# LP4-1.net
KiCad netlist of a schematic drawn in EAGLE
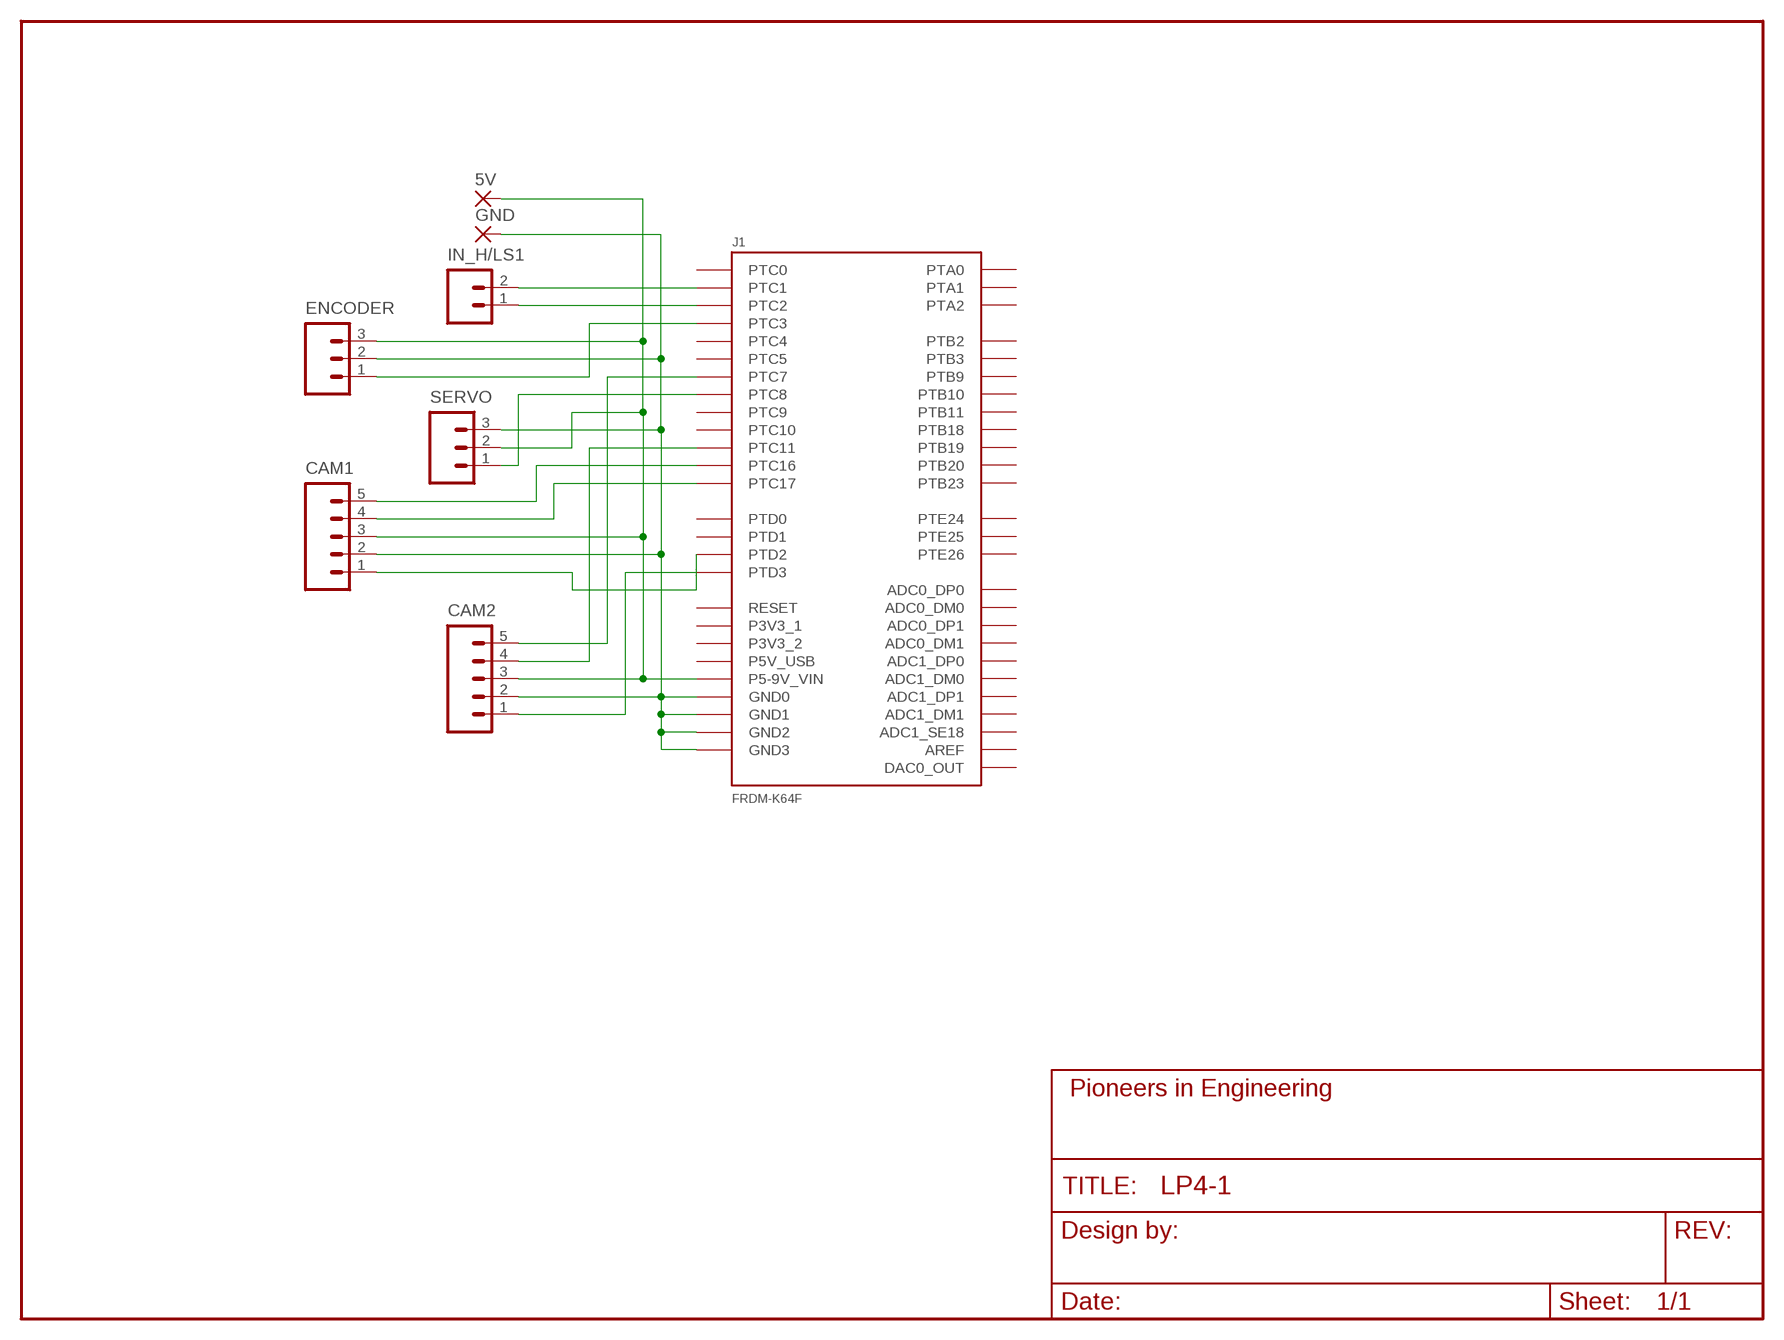
[diagram p0: schematic, sheet 1]

(export (version "E")
  (design (tool "Eeschema 10.0.6"))
  (components
    (comp (ref "5V")
      (value "3,17/1,3")
      (footprint "eagle-import:3,17_1,3")
      (libsource (lib "eagle-import") (part "3,17/1,3"))
    )
    (comp (ref "CAM1")
      (value "M05PTH")
      (footprint "eagle-import:1X05")
      (libsource (lib "eagle-import") (part "M05PTH"))
    )
    (comp (ref "CAM2")
      (value "M05PTH")
      (footprint "eagle-import:1X05")
      (libsource (lib "eagle-import") (part "M05PTH"))
    )
    (comp (ref "ENCODER")
      (value "M03PTH")
      (footprint "eagle-import:1X03")
      (libsource (lib "eagle-import") (part "M03PTH"))
    )
    (comp (ref "GND")
      (value "3,17/1,3")
      (footprint "eagle-import:3,17_1,3")
      (libsource (lib "eagle-import") (part "3,17/1,3"))
    )
    (comp (ref "IN_H/LS1")
      (value "M02PTH")
      (footprint "eagle-import:1X02")
      (libsource (lib "eagle-import") (part "M02PTH"))
    )
    (comp (ref "J1")
      (value "FRDM-K64F")
      (footprint "eagle-import:FRDM-K64F")
      (libsource (lib "eagle-import") (part "FRDM-K64F"))
    )
    (comp (ref "SERVO")
      (value "M03PTH")
      (footprint "eagle-import:1X03")
      (libsource (lib "eagle-import") (part "M03PTH"))
    )
  )
  (nets
    (net (code "1") (name "Net-(5V-P)") (class "Default")
      (node (ref "5V") (pin "1") (pinfunction "P_1") (pintype "passive"))
      (node (ref "CAM1") (pin "3") (pinfunction "3_3") (pintype "passive"))
      (node (ref "CAM2") (pin "3") (pinfunction "3_3") (pintype "passive"))
      (node (ref "ENCODER") (pin "3") (pinfunction "3_3") (pintype "passive"))
      (node (ref "J1") (pin "J3-16") (pinfunction "P5-9V_VIN_J3-16") (pintype "bidirectional"))
      (node (ref "SERVO") (pin "2") (pinfunction "2_2") (pintype "passive"))
    )
    (net (code "2") (name "Net-(GND-P)") (class "Default")
      (node (ref "CAM1") (pin "2") (pinfunction "2_2") (pintype "passive"))
      (node (ref "CAM2") (pin "2") (pinfunction "2_2") (pintype "passive"))
      (node (ref "ENCODER") (pin "2") (pinfunction "2_2") (pintype "passive"))
      (node (ref "GND") (pin "1") (pinfunction "P_1") (pintype "passive"))
      (node (ref "J1") (pin "J2-14") (pinfunction "GND1_J2-14") (pintype "bidirectional"))
      (node (ref "J1") (pin "J2-3") (pinfunction "GND0_J2-3") (pintype "bidirectional"))
      (node (ref "J1") (pin "J3-12") (pinfunction "GND2_J3-12") (pintype "bidirectional"))
      (node (ref "J1") (pin "J3-14") (pinfunction "GND3_J3-14") (pintype "bidirectional"))
      (node (ref "SERVO") (pin "3") (pinfunction "3_3") (pintype "passive"))
    )
    (net (code "3") (name "Net-(J1-PTC1)") (class "Default")
      (node (ref "IN_H/LS1") (pin "2") (pinfunction "2_2") (pintype "passive"))
      (node (ref "J1") (pin "J1-5") (pinfunction "PTC1_J1-5") (pintype "bidirectional"))
    )
    (net (code "4") (name "Net-(J1-PTC2)") (class "Default")
      (node (ref "IN_H/LS1") (pin "1") (pinfunction "1_1") (pintype "passive"))
      (node (ref "J1") (pin "J1-14") (pinfunction "PTC2_J1-14") (pintype "bidirectional"))
    )
    (net (code "5") (name "Net-(J1-PTC3)") (class "Default")
      (node (ref "ENCODER") (pin "1") (pinfunction "1_1") (pintype "passive"))
      (node (ref "J1") (pin "J1-16") (pinfunction "PTC3_J1-16") (pintype "bidirectional"))
    )
    (net (code "6") (name "Net-(J1-PTC7)") (class "Default")
      (node (ref "CAM2") (pin "5") (pinfunction "5_5") (pintype "passive"))
      (node (ref "J1") (pin "J1-13") (pinfunction "PTC7_J1-13") (pintype "bidirectional"))
    )
    (net (code "7") (name "Net-(J1-PTC8)") (class "Default")
      (node (ref "J1") (pin "J1-7") (pinfunction "PTC8_J1-7") (pintype "bidirectional"))
      (node (ref "SERVO") (pin "1") (pinfunction "1_1") (pintype "passive"))
    )
    (net (code "8") (name "Net-(J1-PTC11)") (class "Default")
      (node (ref "CAM2") (pin "4") (pinfunction "4_4") (pintype "passive"))
      (node (ref "J1") (pin "J4-10") (pinfunction "PTC11_J4-10") (pintype "bidirectional"))
    )
    (net (code "9") (name "Net-(J1-PTC16)") (class "Default")
      (node (ref "CAM1") (pin "5") (pinfunction "5_5") (pintype "passive"))
      (node (ref "J1") (pin "J1-2") (pinfunction "PTC16_J1-2") (pintype "bidirectional"))
    )
    (net (code "10") (name "Net-(J1-PTC17)") (class "Default")
      (node (ref "CAM1") (pin "4") (pinfunction "4_4") (pintype "passive"))
      (node (ref "J1") (pin "J1-4") (pinfunction "PTC17_J1-4") (pintype "bidirectional"))
    )
    (net (code "11") (name "Net-(J1-PTD2)") (class "Default")
      (node (ref "CAM1") (pin "1") (pinfunction "1_1") (pintype "passive"))
      (node (ref "J1") (pin "J2-8") (pinfunction "PTD2_J2-8") (pintype "bidirectional"))
    )
    (net (code "12") (name "Net-(J1-PTD3)") (class "Default")
      (node (ref "CAM2") (pin "1") (pinfunction "1_1") (pintype "passive"))
      (node (ref "J1") (pin "J2-10") (pinfunction "PTD3_J2-10") (pintype "bidirectional"))
    )
    (net (code "13") (name "unconnected-(J1-ADC0_DM0-PadJ2-7)") (class "Default")
      (node (ref "J1") (pin "J2-7") (pinfunction "ADC0_DM0_J2-7") (pintype "bidirectional"))
    )
    (net (code "14") (name "unconnected-(J1-ADC0_DM1-PadJ4-3)") (class "Default")
      (node (ref "J1") (pin "J4-3") (pinfunction "ADC0_DM1_J4-3") (pintype "bidirectional"))
    )
    (net (code "15") (name "unconnected-(J1-ADC0_DP0-PadJ2-5)") (class "Default")
      (node (ref "J1") (pin "J2-5") (pinfunction "ADC0_DP0_J2-5") (pintype "bidirectional"))
    )
    (net (code "16") (name "unconnected-(J1-ADC0_DP1-PadJ4-1)") (class "Default")
      (node (ref "J1") (pin "J4-1") (pinfunction "ADC0_DP1_J4-1") (pintype "bidirectional"))
    )
    (net (code "17") (name "unconnected-(J1-ADC1_DM0-PadJ2-13)") (class "Default")
      (node (ref "J1") (pin "J2-13") (pinfunction "ADC1_DM0_J2-13") (pintype "bidirectional"))
    )
    (net (code "18") (name "unconnected-(J1-ADC1_DM1-PadJ4-7)") (class "Default")
      (node (ref "J1") (pin "J4-7") (pinfunction "ADC1_DM1_J4-7") (pintype "bidirectional"))
    )
    (net (code "19") (name "unconnected-(J1-ADC1_DP0-PadJ2-11)") (class "Default")
      (node (ref "J1") (pin "J2-11") (pinfunction "ADC1_DP0_J2-11") (pintype "bidirectional"))
    )
    (net (code "20") (name "unconnected-(J1-ADC1_DP1-PadJ4-5)") (class "Default")
      (node (ref "J1") (pin "J4-5") (pinfunction "ADC1_DP1_J4-5") (pintype "bidirectional"))
    )
    (net (code "21") (name "unconnected-(J1-ADC1_SE18-PadJ2-17)") (class "Default")
      (node (ref "J1") (pin "J2-17") (pinfunction "ADC1_SE18_J2-17") (pintype "bidirectional"))
    )
    (net (code "22") (name "unconnected-(J1-AREF-PadJ2-16)") (class "Default")
      (node (ref "J1") (pin "J2-16") (pinfunction "AREF_J2-16") (pintype "bidirectional"))
    )
    (net (code "23") (name "unconnected-(J1-DAC0_OUT-PadJ4-11)") (class "Default")
      (node (ref "J1") (pin "J4-11") (pinfunction "DAC0_OUT_J4-11") (pintype "bidirectional"))
    )
    (net (code "24") (name "unconnected-(J1-P3V3_1-PadJ3-4)") (class "Default")
      (node (ref "J1") (pin "J3-4") (pinfunction "P3V3_1_J3-4") (pintype "bidirectional"))
    )
    (net (code "25") (name "unconnected-(J1-P3V3_2-PadJ3-8)") (class "Default")
      (node (ref "J1") (pin "J3-8") (pinfunction "P3V3_2_J3-8") (pintype "bidirectional"))
    )
    (net (code "26") (name "unconnected-(J1-P5V_USB-PadJ3-10)") (class "Default")
      (node (ref "J1") (pin "J3-10") (pinfunction "P5V_USB_J3-10") (pintype "bidirectional"))
    )
    (net (code "27") (name "unconnected-(J1-PTA0-PadJ2-2)") (class "Default")
      (node (ref "J1") (pin "J2-2") (pinfunction "PTA0_J2-2") (pintype "bidirectional"))
    )
    (net (code "28") (name "unconnected-(J1-PTA1-PadJ1-8)") (class "Default")
      (node (ref "J1") (pin "J1-8") (pinfunction "PTA1_J1-8") (pintype "bidirectional"))
    )
    (net (code "29") (name "unconnected-(J1-PTA2-PadJ1-12)") (class "Default")
      (node (ref "J1") (pin "J1-12") (pinfunction "PTA2_J1-12") (pintype "bidirectional"))
    )
    (net (code "30") (name "unconnected-(J1-PTB2-PadJ4-2)") (class "Default")
      (node (ref "J1") (pin "J4-2") (pinfunction "PTB2_J4-2") (pintype "bidirectional"))
    )
    (net (code "31") (name "unconnected-(J1-PTB3-PadJ4-4)") (class "Default")
      (node (ref "J1") (pin "J4-4") (pinfunction "PTB3_J4-4") (pintype "bidirectional"))
    )
    (net (code "32") (name "unconnected-(J1-PTB9-PadJ1-6)") (class "Default")
      (node (ref "J1") (pin "J1-6") (pinfunction "PTB9_J1-6") (pintype "bidirectional"))
    )
    (net (code "33") (name "unconnected-(J1-PTB10-PadJ4-6)") (class "Default")
      (node (ref "J1") (pin "J4-6") (pinfunction "PTB10_J4-6") (pintype "bidirectional"))
    )
    (net (code "34") (name "unconnected-(J1-PTB11-PadJ4-8)") (class "Default")
      (node (ref "J1") (pin "J4-8") (pinfunction "PTB11_J4-8") (pintype "bidirectional"))
    )
    (net (code "35") (name "unconnected-(J1-PTB18-PadJ1-1)") (class "Default")
      (node (ref "J1") (pin "J1-1") (pinfunction "PTB18_J1-1") (pintype "bidirectional"))
    )
    (net (code "36") (name "unconnected-(J1-PTB19-PadJ1-3)") (class "Default")
      (node (ref "J1") (pin "J1-3") (pinfunction "PTB19_J1-3") (pintype "bidirectional"))
    )
    (net (code "37") (name "unconnected-(J1-PTB20-PadJ4-9)") (class "Default")
      (node (ref "J1") (pin "J4-9") (pinfunction "PTB20_J4-9") (pintype "bidirectional"))
    )
    (net (code "38") (name "unconnected-(J1-PTB23-PadJ1-10)") (class "Default")
      (node (ref "J1") (pin "J1-10") (pinfunction "PTB23_J1-10") (pintype "bidirectional"))
    )
    (net (code "39") (name "unconnected-(J1-PTC0-PadJ1-11)") (class "Default")
      (node (ref "J1") (pin "J1-11") (pinfunction "PTC0_J1-11") (pintype "bidirectional"))
    )
    (net (code "40") (name "unconnected-(J1-PTC4-PadJ2-4)") (class "Default")
      (node (ref "J1") (pin "J2-4") (pinfunction "PTC4_J2-4") (pintype "bidirectional"))
    )
    (net (code "41") (name "unconnected-(J1-PTC5-PadJ1-15)") (class "Default")
      (node (ref "J1") (pin "J1-15") (pinfunction "PTC5_J1-15") (pintype "bidirectional"))
    )
    (net (code "42") (name "unconnected-(J1-PTC9-PadJ1-9)") (class "Default")
      (node (ref "J1") (pin "J1-9") (pinfunction "PTC9_J1-9") (pintype "bidirectional"))
    )
    (net (code "43") (name "unconnected-(J1-PTC10-PadJ4-12)") (class "Default")
      (node (ref "J1") (pin "J4-12") (pinfunction "PTC10_J4-12") (pintype "bidirectional"))
    )
    (net (code "44") (name "unconnected-(J1-PTD0-PadJ2-6)") (class "Default")
      (node (ref "J1") (pin "J2-6") (pinfunction "PTD0_J2-6") (pintype "bidirectional"))
    )
    (net (code "45") (name "unconnected-(J1-PTD1-PadJ2-12)") (class "Default")
      (node (ref "J1") (pin "J2-12") (pinfunction "PTD1_J2-12") (pintype "bidirectional"))
    )
    (net (code "46") (name "unconnected-(J1-PTE24-PadJ2-20)") (class "Default")
      (node (ref "J1") (pin "J2-20") (pinfunction "PTE24_J2-20") (pintype "bidirectional"))
    )
    (net (code "47") (name "unconnected-(J1-PTE25-PadJ2-18)") (class "Default")
      (node (ref "J1") (pin "J2-18") (pinfunction "PTE25_J2-18") (pintype "bidirectional"))
    )
    (net (code "48") (name "unconnected-(J1-PTE26-PadJ2-1)") (class "Default")
      (node (ref "J1") (pin "J2-1") (pinfunction "PTE26_J2-1") (pintype "bidirectional"))
    )
    (net (code "49") (name "unconnected-(J1-RESET-PadJ3-6)") (class "Default")
      (node (ref "J1") (pin "J3-6") (pinfunction "RESET_J3-6") (pintype "bidirectional"))
    )
  )
)
